# Radio_bridge.net
KiCad netlist of a schematic drawn in EAGLE
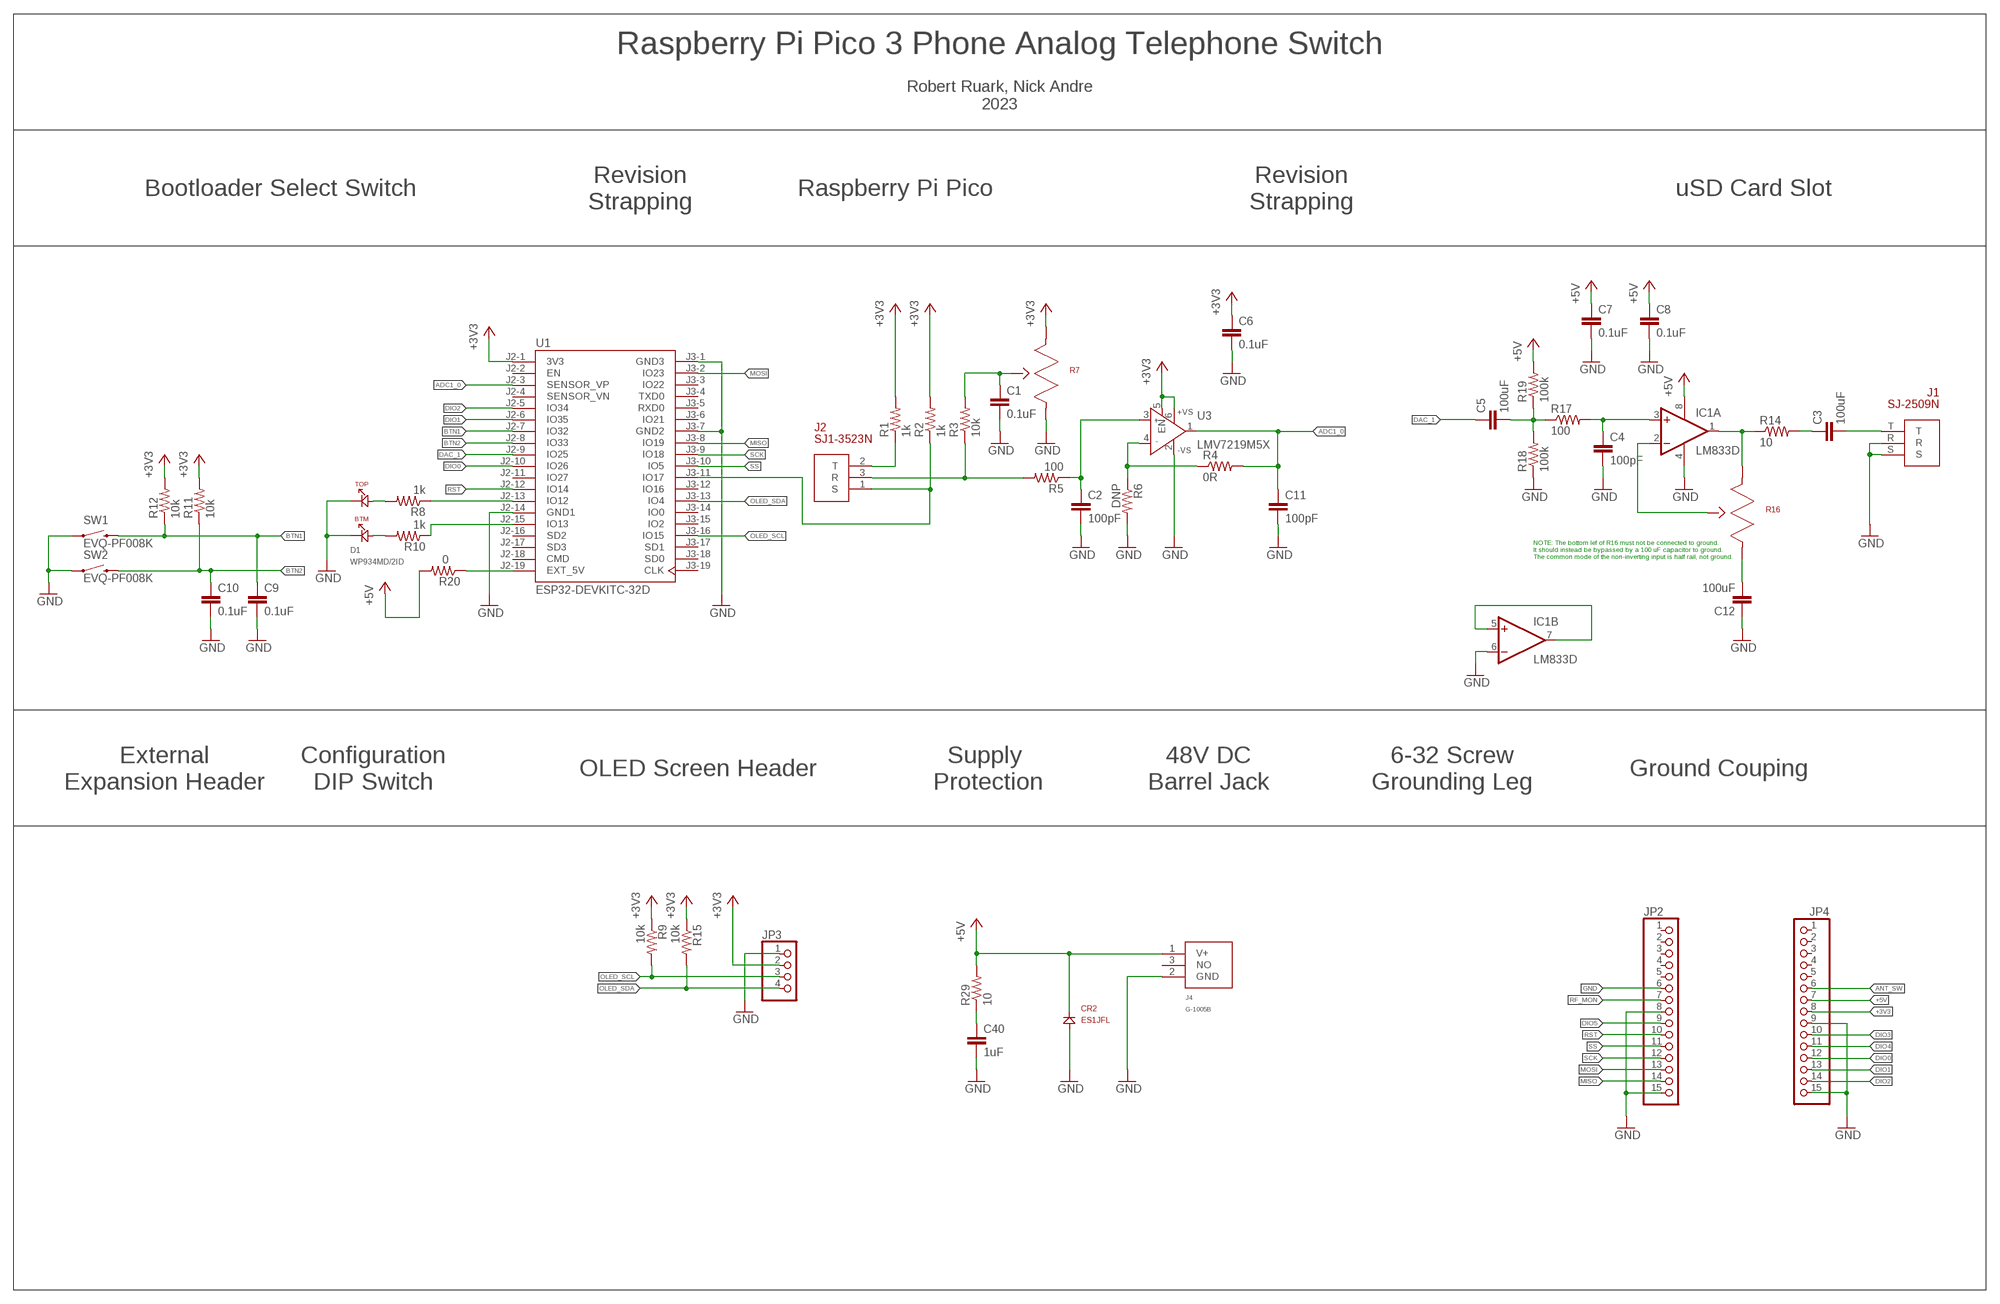
[diagram p0: schematic, sheet 1]
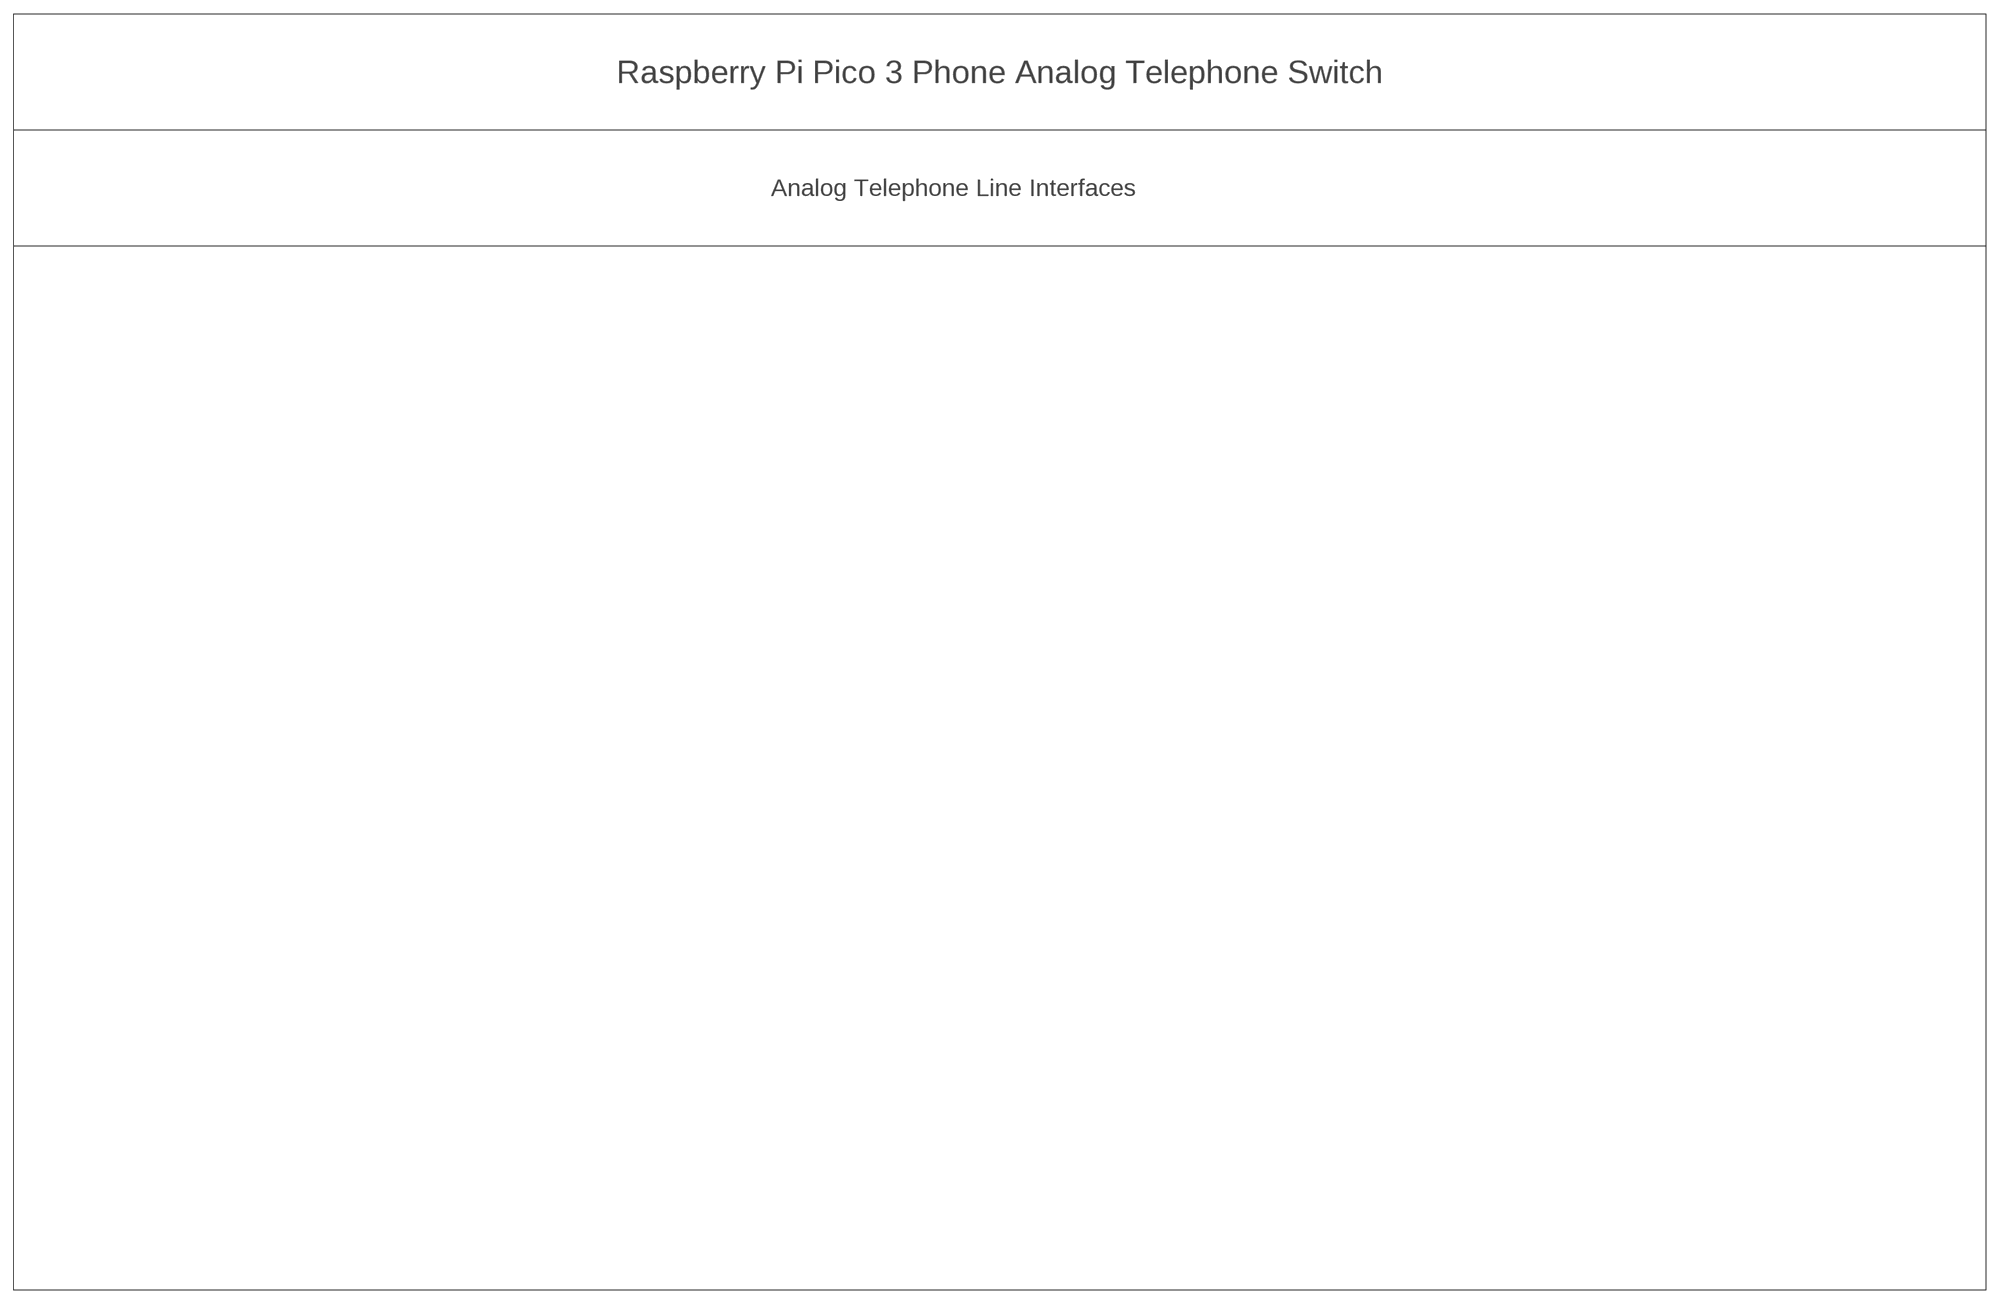
[diagram p1: schematic, sheet 2]

(export (version "E")
  (design (tool "Eeschema 10.0.6"))
  (components
    (comp (ref "C1")
      (value "0.1uF")
      (footprint "eagle-import:0603")
      (libsource (lib "eagle-import") (part "0603_CAPACITOR"))
    )
    (comp (ref "C2")
      (value "100pF")
      (footprint "eagle-import:0603")
      (libsource (lib "eagle-import") (part "0603_CAPACITOR"))
    )
    (comp (ref "C3")
      (value "100uF")
      (footprint "eagle-import:1210")
      (libsource (lib "eagle-import") (part "1210_CAPACITOR"))
    )
    (comp (ref "C4")
      (value "100pF")
      (footprint "eagle-import:0603")
      (libsource (lib "eagle-import") (part "0603_CAPACITOR"))
    )
    (comp (ref "C5")
      (value "100uF")
      (footprint "eagle-import:1210")
      (libsource (lib "eagle-import") (part "1210_CAPACITOR"))
    )
    (comp (ref "C6")
      (value "0.1uF")
      (footprint "eagle-import:0603")
      (libsource (lib "eagle-import") (part "0603_CAPACITOR"))
    )
    (comp (ref "C7")
      (value "0.1uF")
      (footprint "eagle-import:0603")
      (libsource (lib "eagle-import") (part "0603_CAPACITOR"))
    )
    (comp (ref "C8")
      (value "0.1uF")
      (footprint "eagle-import:0603")
      (libsource (lib "eagle-import") (part "0603_CAPACITOR"))
    )
    (comp (ref "C9")
      (value "0.1uF")
      (footprint "eagle-import:0603")
      (libsource (lib "eagle-import") (part "0603_CAPACITOR"))
    )
    (comp (ref "C10")
      (value "0.1uF")
      (footprint "eagle-import:0603")
      (libsource (lib "eagle-import") (part "0603_CAPACITOR"))
    )
    (comp (ref "C11")
      (value "100pF")
      (footprint "eagle-import:0603")
      (libsource (lib "eagle-import") (part "0603_CAPACITOR"))
    )
    (comp (ref "C12")
      (value "100uF")
      (footprint "eagle-import:1210")
      (libsource (lib "eagle-import") (part "1210_CAPACITOR"))
    )
    (comp (ref "C40")
      (value "1uF")
      (footprint "eagle-import:1206")
      (libsource (lib "eagle-import") (part "1206_CAPACITOR"))
    )
    (comp (ref "CR2")
      (value "ES1JFL")
      (footprint "eagle-import:SOD123(AK)")
      (fields (field (name "PARTNO") "ES1JFLCT-ND"))
      (libsource (lib "eagle-import") (part "ES1JFL"))
    )
    (comp (ref "D1")
      (value "WP934MD/2ID")
      (footprint "eagle-import:WP934MD_2ID")
      (libsource (lib "eagle-import") (part "WP934MD/2ID"))
    )
    (comp (ref "IC1")
      (value "LM833D")
      (footprint "eagle-import:SO08")
      (libsource (lib "eagle-import") (part "LM833D"))
    )
    (comp (ref "J1")
      (value "SJ-2509N")
      (footprint "eagle-import:2.5MM_TRS")
      (fields (field (name "PARTNO") "CP-S2509N-ND"))
      (libsource (lib "eagle-import") (part "SJ-2509N"))
    )
    (comp (ref "J2")
      (value "SJ1-3523N")
      (footprint "eagle-import:SJ1-3523N")
      (fields (field (name "PARTNO") "CP1-3523N-ND"))
      (libsource (lib "eagle-import") (part "SJ1-3523N"))
    )
    (comp (ref "J4")
      (value "G-1005B")
      (footprint "eagle-import:G-1005B")
      (fields (field (name "PARTNO") "1939-G-1005B-ND"))
      (libsource (lib "eagle-import") (part "G-1005B"))
    )
    (comp (ref "JP2")
      (value "PINHD-1X15")
      (footprint "eagle-import:1X15")
      (libsource (lib "eagle-import") (part "PINHD-1X15"))
    )
    (comp (ref "JP3")
      (value "PINHD-1X4")
      (footprint "eagle-import:1X04")
      (libsource (lib "eagle-import") (part "PINHD-1X4"))
    )
    (comp (ref "JP4")
      (value "PINHD-1X15")
      (footprint "eagle-import:1X15")
      (libsource (lib "eagle-import") (part "PINHD-1X15"))
    )
    (comp (ref "R1")
      (value "1k")
      (footprint "eagle-import:0603")
      (libsource (lib "eagle-import") (part "0603_RESISTOR"))
    )
    (comp (ref "R2")
      (value "1k")
      (footprint "eagle-import:0603")
      (libsource (lib "eagle-import") (part "0603_RESISTOR"))
    )
    (comp (ref "R3")
      (value "10k")
      (footprint "eagle-import:0603")
      (libsource (lib "eagle-import") (part "0603_RESISTOR"))
    )
    (comp (ref "R4")
      (value "0R")
      (footprint "eagle-import:0603")
      (libsource (lib "eagle-import") (part "0603_RESISTOR"))
    )
    (comp (ref "R5")
      (value "100")
      (footprint "eagle-import:0603")
      (libsource (lib "eagle-import") (part "0603_RESISTOR"))
    )
    (comp (ref "R6")
      (value "DNP")
      (footprint "eagle-import:0603")
      (libsource (lib "eagle-import") (part "0603_RESISTOR"))
    )
    (comp (ref "R7")
      (value "10k")
      (footprint "eagle-import:PTV09")
      (fields (field (name "PARTNO") "PTV09A-4025F-A103-ND"))
      (libsource (lib "eagle-import") (part "PTV09A-4025F-A103"))
    )
    (comp (ref "R8")
      (value "1k")
      (footprint "eagle-import:0603")
      (libsource (lib "eagle-import") (part "0603_RESISTOR"))
    )
    (comp (ref "R9")
      (value "10k")
      (footprint "eagle-import:0603")
      (libsource (lib "eagle-import") (part "0603_RESISTOR"))
    )
    (comp (ref "R10")
      (value "1k")
      (footprint "eagle-import:0603")
      (libsource (lib "eagle-import") (part "0603_RESISTOR"))
    )
    (comp (ref "R11")
      (value "10k")
      (footprint "eagle-import:0603")
      (libsource (lib "eagle-import") (part "0603_RESISTOR"))
    )
    (comp (ref "R12")
      (value "10k")
      (footprint "eagle-import:0603")
      (libsource (lib "eagle-import") (part "0603_RESISTOR"))
    )
    (comp (ref "R14")
      (value "10")
      (footprint "eagle-import:0603")
      (libsource (lib "eagle-import") (part "0603_RESISTOR"))
    )
    (comp (ref "R15")
      (value "10k")
      (footprint "eagle-import:0603")
      (libsource (lib "eagle-import") (part "0603_RESISTOR"))
    )
    (comp (ref "R16")
      (value "10k")
      (footprint "eagle-import:PTV09")
      (fields (field (name "PARTNO") "PTV09A-4025F-A103-ND"))
      (libsource (lib "eagle-import") (part "PTV09A-4025F-A103"))
    )
    (comp (ref "R17")
      (value "100")
      (footprint "eagle-import:0603")
      (libsource (lib "eagle-import") (part "0603_RESISTOR"))
    )
    (comp (ref "R18")
      (value "100k")
      (footprint "eagle-import:0603")
      (libsource (lib "eagle-import") (part "0603_RESISTOR"))
    )
    (comp (ref "R19")
      (value "100k")
      (footprint "eagle-import:0603")
      (libsource (lib "eagle-import") (part "0603_RESISTOR"))
    )
    (comp (ref "R20")
      (value "0")
      (footprint "eagle-import:0603")
      (libsource (lib "eagle-import") (part "0603_RESISTOR"))
    )
    (comp (ref "R29")
      (value "10")
      (footprint "eagle-import:1206")
      (libsource (lib "eagle-import") (part "1206_RESISTOR"))
    )
    (comp (ref "SW1")
      (value "EVQ-PF008K")
      (footprint "eagle-import:EVQ-PF008K")
      (fields (field (name "PARTNO") "P10880S-ND"))
      (libsource (lib "eagle-import") (part "EVQ-PF008K"))
    )
    (comp (ref "SW2")
      (value "EVQ-PF008K")
      (footprint "eagle-import:EVQ-PF008K")
      (fields (field (name "PARTNO") "P10880S-ND"))
      (libsource (lib "eagle-import") (part "EVQ-PF008K"))
    )
    (comp (ref "U1")
      (value "ESP32-DEVKITC-32D")
      (footprint "eagle-import:MODULE_ESP32-DEVKITC-32D")
      (fields (field (name "MF") "Espressif Systems"))
      (libsource (lib "eagle-import") (part "ESP32-DEVKITC-32D"))
    )
    (comp (ref "U3")
      (value "LMV7219M5X")
      (footprint "eagle-import:SOT23-6")
      (fields (field (name "PARTNO") "LMV7219M5X-ND"))
      (libsource (lib "eagle-import") (part "LMV7219M5X"))
    )
  )
  (nets
    (net (code "1") (name "+3V3") (class "Default")
      (node (ref "C6") (pin "1") (pinfunction "1_1") (pintype "passive"))
      (node (ref "JP3") (pin "2") (pinfunction "2_2") (pintype "passive"))
      (node (ref "JP4") (pin "8") (pinfunction "8_8") (pintype "passive"))
      (node (ref "R1") (pin "2") (pinfunction "2_2") (pintype "passive"))
      (node (ref "R11") (pin "2") (pinfunction "2_2") (pintype "passive"))
      (node (ref "R12") (pin "2") (pinfunction "2_2") (pintype "passive"))
      (node (ref "R15") (pin "1") (pinfunction "1_1") (pintype "passive"))
      (node (ref "R2") (pin "2") (pinfunction "2_2") (pintype "passive"))
      (node (ref "R7") (pin "1") (pinfunction "1_1") (pintype "bidirectional"))
      (node (ref "R9") (pin "1") (pinfunction "1_1") (pintype "passive"))
      (node (ref "U1") (pin "J2-1") (pinfunction "3V3_J2-1") (pintype "power_in"))
      (node (ref "U3") (pin "5") (pinfunction "EN_5") (pintype "bidirectional"))
      (node (ref "U3") (pin "6") (pinfunction "+VS_6") (pintype "input"))
    )
    (net (code "2") (name "+5V") (class "Default")
      (node (ref "C7") (pin "1") (pinfunction "1_1") (pintype "passive"))
      (node (ref "C8") (pin "1") (pinfunction "1_1") (pintype "passive"))
      (node (ref "CR2") (pin "K") (pinfunction "K_K") (pintype "bidirectional"))
      (node (ref "IC1") (pin "8") (pinfunction "V+_8") (pintype "power_in"))
      (node (ref "J4") (pin "1") (pinfunction "V+_1") (pintype "bidirectional"))
      (node (ref "JP4") (pin "7") (pinfunction "7_7") (pintype "passive"))
      (node (ref "R19") (pin "2") (pinfunction "2_2") (pintype "passive"))
      (node (ref "R20") (pin "2") (pinfunction "2_2") (pintype "passive"))
      (node (ref "R29") (pin "2") (pinfunction "2_2") (pintype "passive"))
    )
    (net (code "3") (name "ADC1_0") (class "Default")
      (node (ref "C11") (pin "1") (pinfunction "1_1") (pintype "passive"))
      (node (ref "R4") (pin "2") (pinfunction "2_2") (pintype "passive"))
      (node (ref "U1") (pin "J2-3") (pinfunction "SENSOR_VP_J2-3") (pintype "input"))
      (node (ref "U3") (pin "1") (pinfunction "OUT_1") (pintype "output"))
    )
    (net (code "4") (name "ANT_SW") (class "Default")
      (node (ref "JP4") (pin "6") (pinfunction "6_6") (pintype "passive"))
    )
    (net (code "5") (name "BTN1") (class "Default")
      (node (ref "C9") (pin "1") (pinfunction "1_1") (pintype "passive"))
      (node (ref "R12") (pin "1") (pinfunction "1_1") (pintype "passive"))
      (node (ref "SW1") (pin "S2") (pinfunction "2_S2") (pintype "passive"))
      (node (ref "U1") (pin "J2-7") (pinfunction "IO32_J2-7") (pintype "bidirectional"))
    )
    (net (code "6") (name "BTN2") (class "Default")
      (node (ref "C10") (pin "1") (pinfunction "1_1") (pintype "passive"))
      (node (ref "R11") (pin "1") (pinfunction "1_1") (pintype "passive"))
      (node (ref "SW2") (pin "S2") (pinfunction "2_S2") (pintype "passive"))
      (node (ref "U1") (pin "J2-8") (pinfunction "IO33_J2-8") (pintype "bidirectional"))
    )
    (net (code "7") (name "DAC_1") (class "Default")
      (node (ref "C5") (pin "1") (pinfunction "1_1") (pintype "passive"))
      (node (ref "U1") (pin "J2-9") (pinfunction "IO25_J2-9") (pintype "bidirectional"))
    )
    (net (code "8") (name "DIO0") (class "Default")
      (node (ref "JP4") (pin "12") (pinfunction "12_12") (pintype "passive"))
      (node (ref "U1") (pin "J2-10") (pinfunction "IO26_J2-10") (pintype "bidirectional"))
    )
    (net (code "9") (name "DIO1") (class "Default")
      (node (ref "JP4") (pin "13") (pinfunction "13_13") (pintype "passive"))
      (node (ref "U1") (pin "J2-6") (pinfunction "IO35_J2-6") (pintype "bidirectional"))
    )
    (net (code "10") (name "DIO2") (class "Default")
      (node (ref "JP4") (pin "14") (pinfunction "14_14") (pintype "passive"))
      (node (ref "U1") (pin "J2-5") (pinfunction "IO34_J2-5") (pintype "bidirectional"))
    )
    (net (code "11") (name "DIO3") (class "Default")
      (node (ref "JP4") (pin "10") (pinfunction "10_10") (pintype "passive"))
    )
    (net (code "12") (name "DIO4") (class "Default")
      (node (ref "JP4") (pin "11") (pinfunction "11_11") (pintype "passive"))
    )
    (net (code "13") (name "DIO5") (class "Default")
      (node (ref "JP2") (pin "9") (pinfunction "9_9") (pintype "passive"))
    )
    (net (code "14") (name "GND") (class "Default")
      (node (ref "C1") (pin "2") (pinfunction "2_2") (pintype "passive"))
      (node (ref "C10") (pin "2") (pinfunction "2_2") (pintype "passive"))
      (node (ref "C11") (pin "2") (pinfunction "2_2") (pintype "passive"))
      (node (ref "C12") (pin "1") (pinfunction "1_1") (pintype "passive"))
      (node (ref "C2") (pin "2") (pinfunction "2_2") (pintype "passive"))
      (node (ref "C4") (pin "2") (pinfunction "2_2") (pintype "passive"))
      (node (ref "C40") (pin "2") (pinfunction "2_2") (pintype "passive"))
      (node (ref "C6") (pin "2") (pinfunction "2_2") (pintype "passive"))
      (node (ref "C7") (pin "2") (pinfunction "2_2") (pintype "passive"))
      (node (ref "C8") (pin "2") (pinfunction "2_2") (pintype "passive"))
      (node (ref "C9") (pin "2") (pinfunction "2_2") (pintype "passive"))
      (node (ref "CR2") (pin "A") (pinfunction "A_A") (pintype "bidirectional"))
      (node (ref "D1") (pin "K1") (pinfunction "K1_K1") (pintype "bidirectional"))
      (node (ref "D1") (pin "K2") (pinfunction "K2_K2") (pintype "bidirectional"))
      (node (ref "IC1") (pin "4") (pinfunction "V-_4") (pintype "power_in"))
      (node (ref "IC1") (pin "6") (pinfunction "-IN_6") (pintype "input"))
      (node (ref "J1") (pin "R") (pinfunction "R_R") (pintype "passive"))
      (node (ref "J1") (pin "S") (pinfunction "S_S") (pintype "passive"))
      (node (ref "J4") (pin "2") (pinfunction "GND_2") (pintype "bidirectional"))
      (node (ref "JP2") (pin "15") (pinfunction "15_15") (pintype "passive"))
      (node (ref "JP2") (pin "6") (pinfunction "6_6") (pintype "passive"))
      (node (ref "JP2") (pin "8") (pinfunction "8_8") (pintype "passive"))
      (node (ref "JP3") (pin "1") (pinfunction "1_1") (pintype "passive"))
      (node (ref "JP4") (pin "15") (pinfunction "15_15") (pintype "passive"))
      (node (ref "JP4") (pin "9") (pinfunction "9_9") (pintype "passive"))
      (node (ref "R18") (pin "1") (pinfunction "1_1") (pintype "passive"))
      (node (ref "R6") (pin "2") (pinfunction "2_2") (pintype "passive"))
      (node (ref "R7") (pin "3") (pinfunction "3_3") (pintype "bidirectional"))
      (node (ref "SW1") (pin "S1") (pinfunction "1_S1") (pintype "passive"))
      (node (ref "SW2") (pin "S1") (pinfunction "1_S1") (pintype "passive"))
      (node (ref "U1") (pin "J2-14") (pinfunction "GND1_J2-14") (pintype "power_in"))
      (node (ref "U1") (pin "J3-1") (pinfunction "GND3_J3-1") (pintype "power_in"))
      (node (ref "U1") (pin "J3-7") (pinfunction "GND2_J3-7") (pintype "power_in"))
      (node (ref "U3") (pin "2") (pinfunction "-VS_2") (pintype "input"))
    )
    (net (code "15") (name "MISO") (class "Default")
      (node (ref "JP2") (pin "14") (pinfunction "14_14") (pintype "passive"))
      (node (ref "U1") (pin "J3-8") (pinfunction "IO19_J3-8") (pintype "bidirectional"))
    )
    (net (code "16") (name "MOSI") (class "Default")
      (node (ref "JP2") (pin "13") (pinfunction "13_13") (pintype "passive"))
      (node (ref "U1") (pin "J3-2") (pinfunction "IO23_J3-2") (pintype "bidirectional"))
    )
    (net (code "17") (name "Net-(C1-Pad1)") (class "Default")
      (node (ref "C1") (pin "1") (pinfunction "1_1") (pintype "passive"))
      (node (ref "R3") (pin "2") (pinfunction "2_2") (pintype "passive"))
      (node (ref "R7") (pin "2") (pinfunction "2_2") (pintype "bidirectional"))
    )
    (net (code "18") (name "Net-(C3-Pad1)") (class "Default")
      (node (ref "C3") (pin "1") (pinfunction "1_1") (pintype "passive"))
      (node (ref "R14") (pin "2") (pinfunction "2_2") (pintype "passive"))
    )
    (net (code "19") (name "Net-(C3-Pad2)") (class "Default")
      (node (ref "C3") (pin "2") (pinfunction "2_2") (pintype "passive"))
      (node (ref "J1") (pin "T") (pinfunction "T_T") (pintype "passive"))
    )
    (net (code "20") (name "Net-(C5-Pad2)") (class "Default")
      (node (ref "C5") (pin "2") (pinfunction "2_2") (pintype "passive"))
      (node (ref "R17") (pin "1") (pinfunction "1_1") (pintype "passive"))
      (node (ref "R18") (pin "2") (pinfunction "2_2") (pintype "passive"))
      (node (ref "R19") (pin "1") (pinfunction "1_1") (pintype "passive"))
    )
    (net (code "21") (name "Net-(C12-Pad2)") (class "Default")
      (node (ref "C12") (pin "2") (pinfunction "2_2") (pintype "passive"))
      (node (ref "R16") (pin "3") (pinfunction "3_3") (pintype "bidirectional"))
    )
    (net (code "22") (name "Net-(C40-Pad1)") (class "Default")
      (node (ref "C40") (pin "1") (pinfunction "1_1") (pintype "passive"))
      (node (ref "R29") (pin "1") (pinfunction "1_1") (pintype "passive"))
    )
    (net (code "23") (name "Net-(D1-PadA1)") (class "Default")
      (node (ref "D1") (pin "A1") (pinfunction "A1_A1") (pintype "bidirectional"))
      (node (ref "R10") (pin "2") (pinfunction "2_2") (pintype "passive"))
    )
    (net (code "24") (name "Net-(D1-PadA2)") (class "Default")
      (node (ref "D1") (pin "A2") (pinfunction "A2_A2") (pintype "bidirectional"))
      (node (ref "R8") (pin "2") (pinfunction "2_2") (pintype "passive"))
    )
    (net (code "25") (name "Net-(IC1A-+IN)") (class "Default")
      (node (ref "C4") (pin "1") (pinfunction "1_1") (pintype "passive"))
      (node (ref "IC1") (pin "3") (pinfunction "+IN_3") (pintype "input"))
      (node (ref "R17") (pin "2") (pinfunction "2_2") (pintype "passive"))
    )
    (net (code "26") (name "Net-(IC1A--IN)") (class "Default")
      (node (ref "IC1") (pin "2") (pinfunction "-IN_2") (pintype "input"))
      (node (ref "R16") (pin "2") (pinfunction "2_2") (pintype "bidirectional"))
    )
    (net (code "27") (name "Net-(IC1A-OUT)") (class "Default")
      (node (ref "IC1") (pin "1") (pinfunction "OUT_1") (pintype "output"))
      (node (ref "R14") (pin "1") (pinfunction "1_1") (pintype "passive"))
      (node (ref "R16") (pin "1") (pinfunction "1_1") (pintype "bidirectional"))
    )
    (net (code "28") (name "Net-(IC1B-+IN)") (class "Default")
      (node (ref "IC1") (pin "5") (pinfunction "+IN_5") (pintype "input"))
      (node (ref "IC1") (pin "7") (pinfunction "OUT_7") (pintype "output"))
    )
    (net (code "29") (name "Net-(J2-R)") (class "Default")
      (node (ref "J2") (pin "3") (pinfunction "R_3") (pintype "passive"))
      (node (ref "R3") (pin "1") (pinfunction "1_1") (pintype "passive"))
      (node (ref "R5") (pin "2") (pinfunction "2_2") (pintype "passive"))
    )
    (net (code "30") (name "Net-(J2-S)") (class "Default")
      (node (ref "J2") (pin "1") (pinfunction "S_1") (pintype "passive"))
      (node (ref "R2") (pin "1") (pinfunction "1_1") (pintype "passive"))
      (node (ref "U1") (pin "J3-11") (pinfunction "IO17_J3-11") (pintype "bidirectional"))
    )
    (net (code "31") (name "Net-(J2-T)") (class "Default")
      (node (ref "J2") (pin "2") (pinfunction "T_2") (pintype "passive"))
      (node (ref "R1") (pin "1") (pinfunction "1_1") (pintype "passive"))
    )
    (net (code "32") (name "Net-(U1-EXT_5V)") (class "Default")
      (node (ref "R20") (pin "1") (pinfunction "1_1") (pintype "passive"))
      (node (ref "U1") (pin "J2-19") (pinfunction "EXT_5V_J2-19") (pintype "power_in"))
    )
    (net (code "33") (name "Net-(U1-IO12)") (class "Default")
      (node (ref "R8") (pin "1") (pinfunction "1_1") (pintype "passive"))
      (node (ref "U1") (pin "J2-13") (pinfunction "IO12_J2-13") (pintype "bidirectional"))
    )
    (net (code "34") (name "Net-(U1-IO13)") (class "Default")
      (node (ref "R10") (pin "1") (pinfunction "1_1") (pintype "passive"))
      (node (ref "U1") (pin "J2-15") (pinfunction "IO13_J2-15") (pintype "bidirectional"))
    )
    (net (code "35") (name "Net-(U3-IN+)") (class "Default")
      (node (ref "C2") (pin "1") (pinfunction "1_1") (pintype "passive"))
      (node (ref "R5") (pin "1") (pinfunction "1_1") (pintype "passive"))
      (node (ref "U3") (pin "3") (pinfunction "IN+_3") (pintype "input"))
    )
    (net (code "36") (name "Net-(U3-IN-)") (class "Default")
      (node (ref "R4") (pin "1") (pinfunction "1_1") (pintype "passive"))
      (node (ref "R6") (pin "1") (pinfunction "1_1") (pintype "passive"))
      (node (ref "U3") (pin "4") (pinfunction "IN-_4") (pintype "input"))
    )
    (net (code "37") (name "OLED_SCL") (class "Default")
      (node (ref "JP3") (pin "3") (pinfunction "3_3") (pintype "passive"))
      (node (ref "R9") (pin "2") (pinfunction "2_2") (pintype "passive"))
      (node (ref "U1") (pin "J3-16") (pinfunction "IO15_J3-16") (pintype "bidirectional"))
    )
    (net (code "38") (name "OLED_SDA") (class "Default")
      (node (ref "JP3") (pin "4") (pinfunction "4_4") (pintype "passive"))
      (node (ref "R15") (pin "2") (pinfunction "2_2") (pintype "passive"))
      (node (ref "U1") (pin "J3-13") (pinfunction "IO4_J3-13") (pintype "bidirectional"))
    )
    (net (code "39") (name "RF_MON") (class "Default")
      (node (ref "JP2") (pin "7") (pinfunction "7_7") (pintype "passive"))
    )
    (net (code "40") (name "RST") (class "Default")
      (node (ref "JP2") (pin "10") (pinfunction "10_10") (pintype "passive"))
      (node (ref "U1") (pin "J2-12") (pinfunction "IO14_J2-12") (pintype "bidirectional"))
    )
    (net (code "41") (name "SCK") (class "Default")
      (node (ref "JP2") (pin "12") (pinfunction "12_12") (pintype "passive"))
      (node (ref "U1") (pin "J3-9") (pinfunction "IO18_J3-9") (pintype "bidirectional"))
    )
    (net (code "42") (name "SS") (class "Default")
      (node (ref "JP2") (pin "11") (pinfunction "11_11") (pintype "passive"))
      (node (ref "U1") (pin "J3-10") (pinfunction "IO5_J3-10") (pintype "bidirectional"))
    )
    (net (code "43") (name "unconnected-(J4-NO-Pad3)") (class "Default")
      (node (ref "J4") (pin "3") (pinfunction "NO_3") (pintype "bidirectional"))
    )
    (net (code "44") (name "unconnected-(JP2-Pad1)") (class "Default")
      (node (ref "JP2") (pin "1") (pinfunction "1_1") (pintype "passive"))
    )
    (net (code "45") (name "unconnected-(JP2-Pad2)") (class "Default")
      (node (ref "JP2") (pin "2") (pinfunction "2_2") (pintype "passive"))
    )
    (net (code "46") (name "unconnected-(JP2-Pad3)") (class "Default")
      (node (ref "JP2") (pin "3") (pinfunction "3_3") (pintype "passive"))
    )
    (net (code "47") (name "unconnected-(JP2-Pad4)") (class "Default")
      (node (ref "JP2") (pin "4") (pinfunction "4_4") (pintype "passive"))
    )
    (net (code "48") (name "unconnected-(JP2-Pad5)") (class "Default")
      (node (ref "JP2") (pin "5") (pinfunction "5_5") (pintype "passive"))
    )
    (net (code "49") (name "unconnected-(JP4-Pad1)") (class "Default")
      (node (ref "JP4") (pin "1") (pinfunction "1_1") (pintype "passive"))
    )
    (net (code "50") (name "unconnected-(JP4-Pad2)") (class "Default")
      (node (ref "JP4") (pin "2") (pinfunction "2_2") (pintype "passive"))
    )
    (net (code "51") (name "unconnected-(JP4-Pad3)") (class "Default")
      (node (ref "JP4") (pin "3") (pinfunction "3_3") (pintype "passive"))
    )
    (net (code "52") (name "unconnected-(JP4-Pad4)") (class "Default")
      (node (ref "JP4") (pin "4") (pinfunction "4_4") (pintype "passive"))
    )
    (net (code "53") (name "unconnected-(JP4-Pad5)") (class "Default")
      (node (ref "JP4") (pin "5") (pinfunction "5_5") (pintype "passive"))
    )
    (net (code "54") (name "unconnected-(U1-CLK-PadJ3-19)") (class "Default")
      (node (ref "U1") (pin "J3-19") (pinfunction "CLK_J3-19") (pintype "input"))
    )
    (net (code "55") (name "unconnected-(U1-CMD-PadJ2-18)") (class "Default")
      (node (ref "U1") (pin "J2-18") (pinfunction "CMD_J2-18") (pintype "bidirectional"))
    )
    (net (code "56") (name "unconnected-(U1-EN-PadJ2-2)") (class "Default")
      (node (ref "U1") (pin "J2-2") (pinfunction "EN_J2-2") (pintype "input"))
    )
    (net (code "57") (name "unconnected-(U1-IO0-PadJ3-14)") (class "Default")
      (node (ref "U1") (pin "J3-14") (pinfunction "IO0_J3-14") (pintype "bidirectional"))
    )
    (net (code "58") (name "unconnected-(U1-IO2-PadJ3-15)") (class "Default")
      (node (ref "U1") (pin "J3-15") (pinfunction "IO2_J3-15") (pintype "bidirectional"))
    )
    (net (code "59") (name "unconnected-(U1-IO16-PadJ3-12)") (class "Default")
      (node (ref "U1") (pin "J3-12") (pinfunction "IO16_J3-12") (pintype "bidirectional"))
    )
    (net (code "60") (name "unconnected-(U1-IO21-PadJ3-6)") (class "Default")
      (node (ref "U1") (pin "J3-6") (pinfunction "IO21_J3-6") (pintype "bidirectional"))
    )
    (net (code "61") (name "unconnected-(U1-IO22-PadJ3-3)") (class "Default")
      (node (ref "U1") (pin "J3-3") (pinfunction "IO22_J3-3") (pintype "bidirectional"))
    )
    (net (code "62") (name "unconnected-(U1-IO27-PadJ2-11)") (class "Default")
      (node (ref "U1") (pin "J2-11") (pinfunction "IO27_J2-11") (pintype "bidirectional"))
    )
    (net (code "63") (name "unconnected-(U1-RXD0-PadJ3-5)") (class "Default")
      (node (ref "U1") (pin "J3-5") (pinfunction "RXD0_J3-5") (pintype "input"))
    )
    (net (code "64") (name "unconnected-(U1-SD0-PadJ3-18)") (class "Default")
      (node (ref "U1") (pin "J3-18") (pinfunction "SD0_J3-18") (pintype "bidirectional"))
    )
    (net (code "65") (name "unconnected-(U1-SD1-PadJ3-17)") (class "Default")
      (node (ref "U1") (pin "J3-17") (pinfunction "SD1_J3-17") (pintype "bidirectional"))
    )
    (net (code "66") (name "unconnected-(U1-SD2-PadJ2-16)") (class "Default")
      (node (ref "U1") (pin "J2-16") (pinfunction "SD2_J2-16") (pintype "bidirectional"))
    )
    (net (code "67") (name "unconnected-(U1-SD3-PadJ2-17)") (class "Default")
      (node (ref "U1") (pin "J2-17") (pinfunction "SD3_J2-17") (pintype "bidirectional"))
    )
    (net (code "68") (name "unconnected-(U1-SENSOR_VN-PadJ2-4)") (class "Default")
      (node (ref "U1") (pin "J2-4") (pinfunction "SENSOR_VN_J2-4") (pintype "input"))
    )
    (net (code "69") (name "unconnected-(U1-TXD0-PadJ3-4)") (class "Default")
      (node (ref "U1") (pin "J3-4") (pinfunction "TXD0_J3-4") (pintype "output"))
    )
  )
)
